# connector-32ch.net
KiCad netlist of a schematic drawn in EAGLE
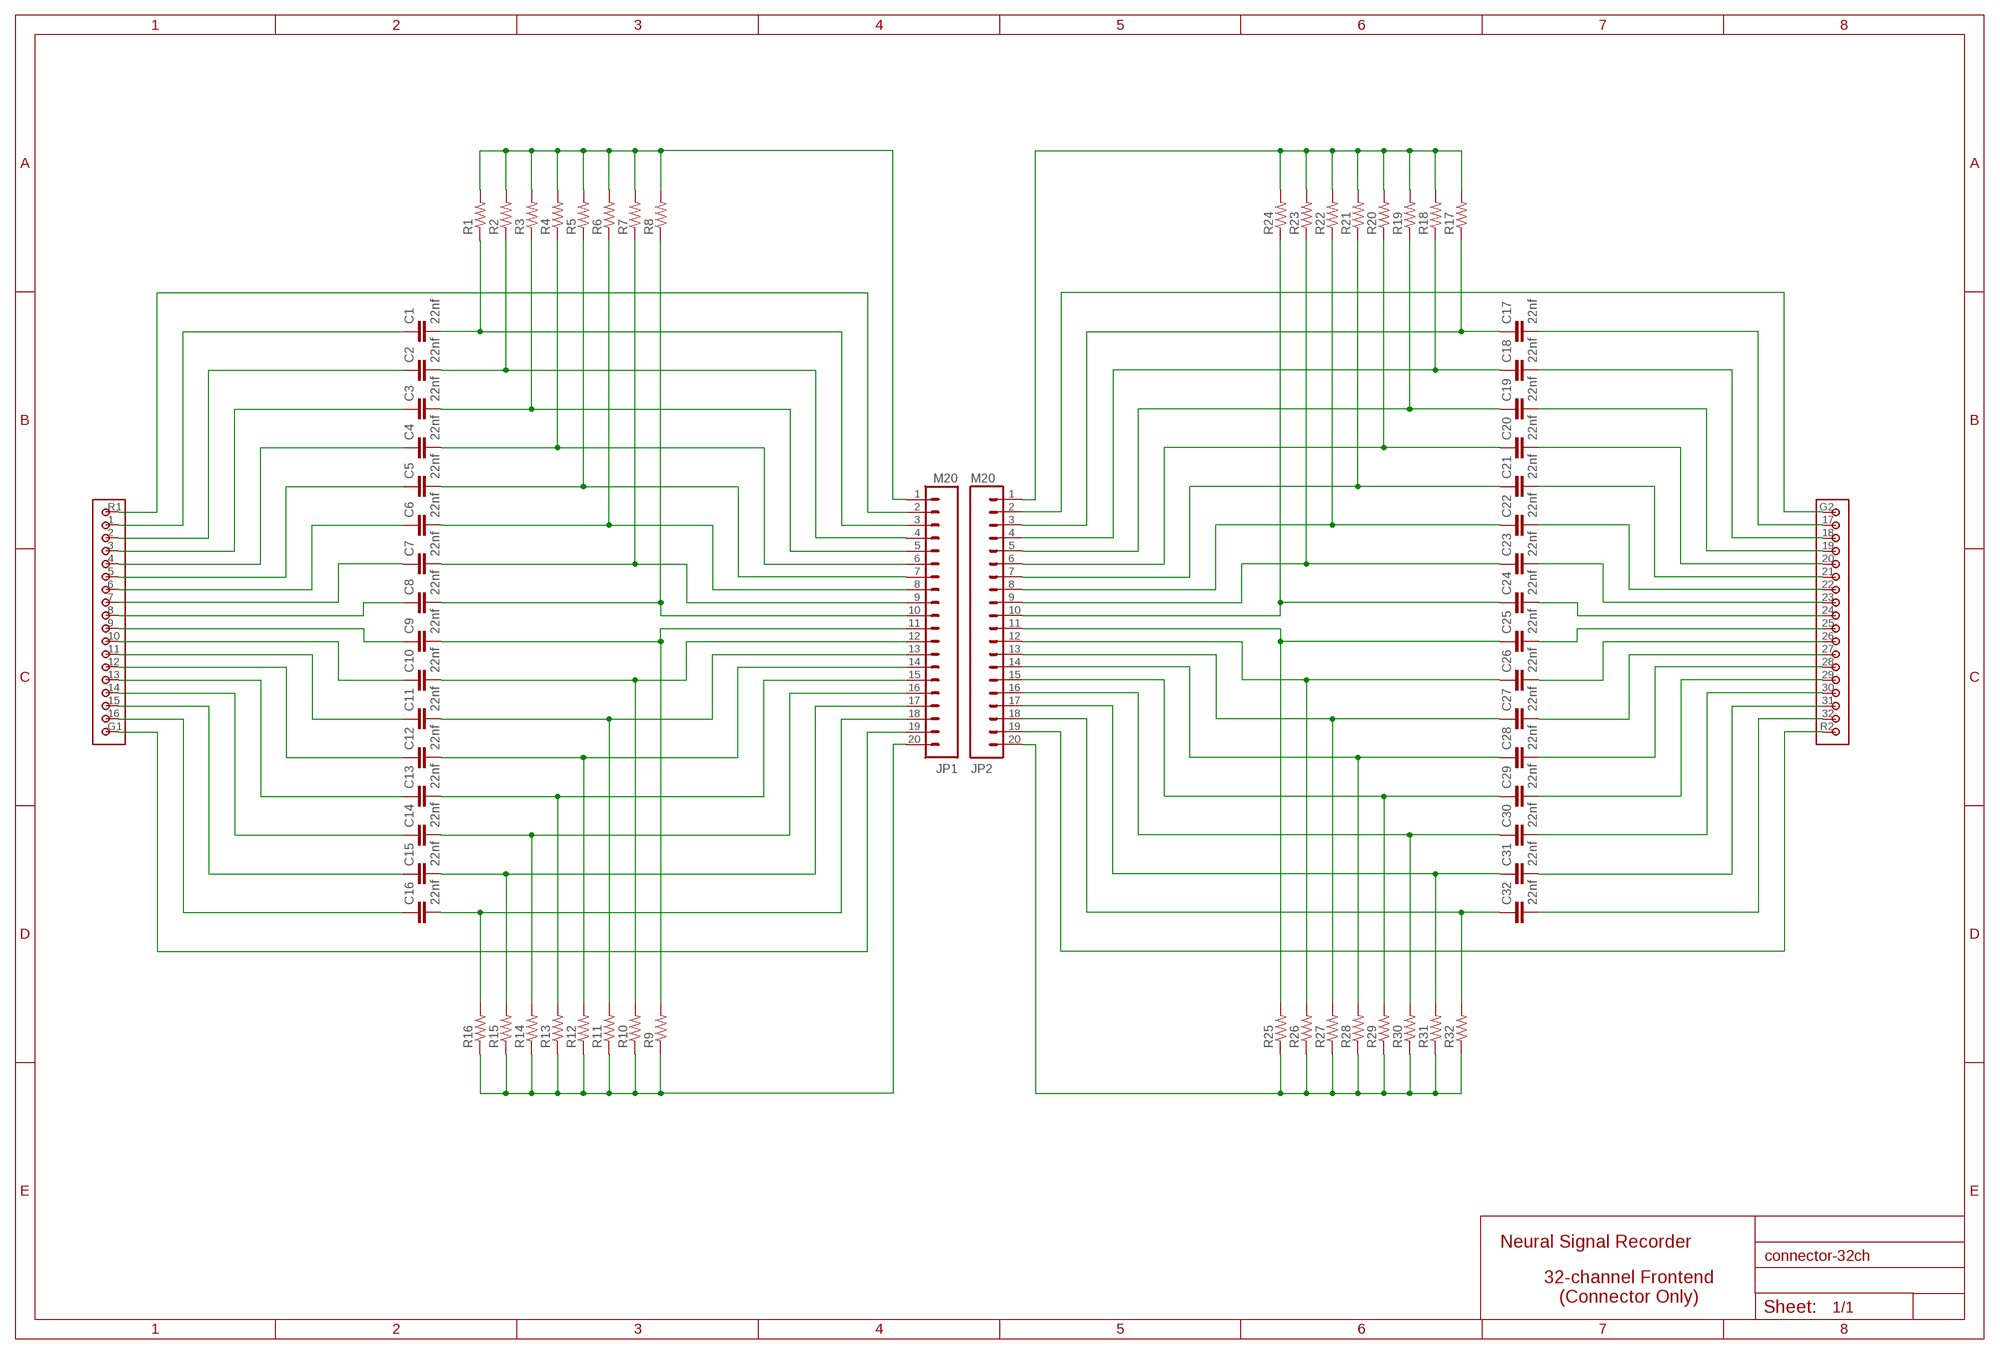
[diagram p0: schematic, sheet 1]

(export (version "E")
  (design (tool "Eeschema 10.0.6"))
  (components
    (comp (ref "C1")
      (value "22nf")
      (footprint "eagle-import:C0402")
      (libsource (lib "eagle-import") (part "C-EUC0402"))
    )
    (comp (ref "C2")
      (value "22nf")
      (footprint "eagle-import:C0402")
      (libsource (lib "eagle-import") (part "C-EUC0402"))
    )
    (comp (ref "C3")
      (value "22nf")
      (footprint "eagle-import:C0402")
      (libsource (lib "eagle-import") (part "C-EUC0402"))
    )
    (comp (ref "C4")
      (value "22nf")
      (footprint "eagle-import:C0402")
      (libsource (lib "eagle-import") (part "C-EUC0402"))
    )
    (comp (ref "C5")
      (value "22nf")
      (footprint "eagle-import:C0402")
      (libsource (lib "eagle-import") (part "C-EUC0402"))
    )
    (comp (ref "C6")
      (value "22nf")
      (footprint "eagle-import:C0402")
      (libsource (lib "eagle-import") (part "C-EUC0402"))
    )
    (comp (ref "C7")
      (value "22nf")
      (footprint "eagle-import:C0402")
      (libsource (lib "eagle-import") (part "C-EUC0402"))
    )
    (comp (ref "C8")
      (value "22nf")
      (footprint "eagle-import:C0402")
      (libsource (lib "eagle-import") (part "C-EUC0402"))
    )
    (comp (ref "C9")
      (value "22nf")
      (footprint "eagle-import:C0402")
      (libsource (lib "eagle-import") (part "C-EUC0402"))
    )
    (comp (ref "C10")
      (value "22nf")
      (footprint "eagle-import:C0402")
      (libsource (lib "eagle-import") (part "C-EUC0402"))
    )
    (comp (ref "C11")
      (value "22nf")
      (footprint "eagle-import:C0402")
      (libsource (lib "eagle-import") (part "C-EUC0402"))
    )
    (comp (ref "C12")
      (value "22nf")
      (footprint "eagle-import:C0402")
      (libsource (lib "eagle-import") (part "C-EUC0402"))
    )
    (comp (ref "C13")
      (value "22nf")
      (footprint "eagle-import:C0402")
      (libsource (lib "eagle-import") (part "C-EUC0402"))
    )
    (comp (ref "C14")
      (value "22nf")
      (footprint "eagle-import:C0402")
      (libsource (lib "eagle-import") (part "C-EUC0402"))
    )
    (comp (ref "C15")
      (value "22nf")
      (footprint "eagle-import:C0402")
      (libsource (lib "eagle-import") (part "C-EUC0402"))
    )
    (comp (ref "C16")
      (value "22nf")
      (footprint "eagle-import:C0402")
      (libsource (lib "eagle-import") (part "C-EUC0402"))
    )
    (comp (ref "C17")
      (value "22nf")
      (footprint "eagle-import:C0402")
      (libsource (lib "eagle-import") (part "C-EUC0402"))
    )
    (comp (ref "C18")
      (value "22nf")
      (footprint "eagle-import:C0402")
      (libsource (lib "eagle-import") (part "C-EUC0402"))
    )
    (comp (ref "C19")
      (value "22nf")
      (footprint "eagle-import:C0402")
      (libsource (lib "eagle-import") (part "C-EUC0402"))
    )
    (comp (ref "C20")
      (value "22nf")
      (footprint "eagle-import:C0402")
      (libsource (lib "eagle-import") (part "C-EUC0402"))
    )
    (comp (ref "C21")
      (value "22nf")
      (footprint "eagle-import:C0402")
      (libsource (lib "eagle-import") (part "C-EUC0402"))
    )
    (comp (ref "C22")
      (value "22nf")
      (footprint "eagle-import:C0402")
      (libsource (lib "eagle-import") (part "C-EUC0402"))
    )
    (comp (ref "C23")
      (value "22nf")
      (footprint "eagle-import:C0402")
      (libsource (lib "eagle-import") (part "C-EUC0402"))
    )
    (comp (ref "C24")
      (value "22nf")
      (footprint "eagle-import:C0402")
      (libsource (lib "eagle-import") (part "C-EUC0402"))
    )
    (comp (ref "C25")
      (value "22nf")
      (footprint "eagle-import:C0402")
      (libsource (lib "eagle-import") (part "C-EUC0402"))
    )
    (comp (ref "C26")
      (value "22nf")
      (footprint "eagle-import:C0402")
      (libsource (lib "eagle-import") (part "C-EUC0402"))
    )
    (comp (ref "C27")
      (value "22nf")
      (footprint "eagle-import:C0402")
      (libsource (lib "eagle-import") (part "C-EUC0402"))
    )
    (comp (ref "C28")
      (value "22nf")
      (footprint "eagle-import:C0402")
      (libsource (lib "eagle-import") (part "C-EUC0402"))
    )
    (comp (ref "C29")
      (value "22nf")
      (footprint "eagle-import:C0402")
      (libsource (lib "eagle-import") (part "C-EUC0402"))
    )
    (comp (ref "C30")
      (value "22nf")
      (footprint "eagle-import:C0402")
      (libsource (lib "eagle-import") (part "C-EUC0402"))
    )
    (comp (ref "C31")
      (value "22nf")
      (footprint "eagle-import:C0402")
      (libsource (lib "eagle-import") (part "C-EUC0402"))
    )
    (comp (ref "C32")
      (value "22nf")
      (footprint "eagle-import:C0402")
      (libsource (lib "eagle-import") (part "C-EUC0402"))
    )
    (comp (ref "JP1")
      (value "M20")
      (footprint "eagle-import:1X20")
      (libsource (lib "eagle-import") (part "M20"))
    )
    (comp (ref "JP2")
      (value "M20")
      (footprint "eagle-import:1X20")
      (libsource (lib "eagle-import") (part "M20"))
    )
    (comp (ref "R1")
      (value "R-US_R0402")
      (footprint "eagle-import:R0402")
      (libsource (lib "eagle-import") (part "R-US_R0402"))
    )
    (comp (ref "R2")
      (value "R-US_R0402")
      (footprint "eagle-import:R0402")
      (libsource (lib "eagle-import") (part "R-US_R0402"))
    )
    (comp (ref "R3")
      (value "R-US_R0402")
      (footprint "eagle-import:R0402")
      (libsource (lib "eagle-import") (part "R-US_R0402"))
    )
    (comp (ref "R4")
      (value "R-US_R0402")
      (footprint "eagle-import:R0402")
      (libsource (lib "eagle-import") (part "R-US_R0402"))
    )
    (comp (ref "R5")
      (value "R-US_R0402")
      (footprint "eagle-import:R0402")
      (libsource (lib "eagle-import") (part "R-US_R0402"))
    )
    (comp (ref "R6")
      (value "R-US_R0402")
      (footprint "eagle-import:R0402")
      (libsource (lib "eagle-import") (part "R-US_R0402"))
    )
    (comp (ref "R7")
      (value "R-US_R0402")
      (footprint "eagle-import:R0402")
      (libsource (lib "eagle-import") (part "R-US_R0402"))
    )
    (comp (ref "R8")
      (value "R-US_R0402")
      (footprint "eagle-import:R0402")
      (libsource (lib "eagle-import") (part "R-US_R0402"))
    )
    (comp (ref "R9")
      (value "R-US_R0402")
      (footprint "eagle-import:R0402")
      (libsource (lib "eagle-import") (part "R-US_R0402"))
    )
    (comp (ref "R10")
      (value "R-US_R0402")
      (footprint "eagle-import:R0402")
      (libsource (lib "eagle-import") (part "R-US_R0402"))
    )
    (comp (ref "R11")
      (value "R-US_R0402")
      (footprint "eagle-import:R0402")
      (libsource (lib "eagle-import") (part "R-US_R0402"))
    )
    (comp (ref "R12")
      (value "R-US_R0402")
      (footprint "eagle-import:R0402")
      (libsource (lib "eagle-import") (part "R-US_R0402"))
    )
    (comp (ref "R13")
      (value "R-US_R0402")
      (footprint "eagle-import:R0402")
      (libsource (lib "eagle-import") (part "R-US_R0402"))
    )
    (comp (ref "R14")
      (value "R-US_R0402")
      (footprint "eagle-import:R0402")
      (libsource (lib "eagle-import") (part "R-US_R0402"))
    )
    (comp (ref "R15")
      (value "R-US_R0402")
      (footprint "eagle-import:R0402")
      (libsource (lib "eagle-import") (part "R-US_R0402"))
    )
    (comp (ref "R16")
      (value "R-US_R0402")
      (footprint "eagle-import:R0402")
      (libsource (lib "eagle-import") (part "R-US_R0402"))
    )
    (comp (ref "R17")
      (value "R-US_R0402")
      (footprint "eagle-import:R0402")
      (libsource (lib "eagle-import") (part "R-US_R0402"))
    )
    (comp (ref "R18")
      (value "R-US_R0402")
      (footprint "eagle-import:R0402")
      (libsource (lib "eagle-import") (part "R-US_R0402"))
    )
    (comp (ref "R19")
      (value "R-US_R0402")
      (footprint "eagle-import:R0402")
      (libsource (lib "eagle-import") (part "R-US_R0402"))
    )
    (comp (ref "R20")
      (value "R-US_R0402")
      (footprint "eagle-import:R0402")
      (libsource (lib "eagle-import") (part "R-US_R0402"))
    )
    (comp (ref "R21")
      (value "R-US_R0402")
      (footprint "eagle-import:R0402")
      (libsource (lib "eagle-import") (part "R-US_R0402"))
    )
    (comp (ref "R22")
      (value "R-US_R0402")
      (footprint "eagle-import:R0402")
      (libsource (lib "eagle-import") (part "R-US_R0402"))
    )
    (comp (ref "R23")
      (value "R-US_R0402")
      (footprint "eagle-import:R0402")
      (libsource (lib "eagle-import") (part "R-US_R0402"))
    )
    (comp (ref "R24")
      (value "R-US_R0402")
      (footprint "eagle-import:R0402")
      (libsource (lib "eagle-import") (part "R-US_R0402"))
    )
    (comp (ref "R25")
      (value "R-US_R0402")
      (footprint "eagle-import:R0402")
      (libsource (lib "eagle-import") (part "R-US_R0402"))
    )
    (comp (ref "R26")
      (value "R-US_R0402")
      (footprint "eagle-import:R0402")
      (libsource (lib "eagle-import") (part "R-US_R0402"))
    )
    (comp (ref "R27")
      (value "R-US_R0402")
      (footprint "eagle-import:R0402")
      (libsource (lib "eagle-import") (part "R-US_R0402"))
    )
    (comp (ref "R28")
      (value "R-US_R0402")
      (footprint "eagle-import:R0402")
      (libsource (lib "eagle-import") (part "R-US_R0402"))
    )
    (comp (ref "R29")
      (value "R-US_R0402")
      (footprint "eagle-import:R0402")
      (libsource (lib "eagle-import") (part "R-US_R0402"))
    )
    (comp (ref "R30")
      (value "R-US_R0402")
      (footprint "eagle-import:R0402")
      (libsource (lib "eagle-import") (part "R-US_R0402"))
    )
    (comp (ref "R31")
      (value "R-US_R0402")
      (footprint "eagle-import:R0402")
      (libsource (lib "eagle-import") (part "R-US_R0402"))
    )
    (comp (ref "R32")
      (value "R-US_R0402")
      (footprint "eagle-import:R0402")
      (libsource (lib "eagle-import") (part "R-US_R0402"))
    )
    (comp (ref "X1")
      (value "OMNETICS_36PAD")
      (footprint "eagle-import:OMNETICS36PADSMT")
      (libsource (lib "eagle-import") (part "OMNETICS_36PAD"))
    )
  )
  (nets
    (net (code "1") (name "/G") (class "Default")
      (node (ref "JP1") (pin "2") (pinfunction "2_2") (pintype "passive"))
      (node (ref "JP2") (pin "19") (pinfunction "19_19") (pintype "passive"))
      (node (ref "X1") (pin "R1") (pinfunction "P$1_R1") (pintype "passive"))
      (node (ref "X1") (pin "R2") (pinfunction "P$18_R2") (pintype "passive"))
    )
    (net (code "2") (name "/R") (class "Default")
      (node (ref "JP1") (pin "19") (pinfunction "19_19") (pintype "passive"))
      (node (ref "JP2") (pin "2") (pinfunction "2_2") (pintype "passive"))
      (node (ref "X1") (pin "G1") (pinfunction "P$18_G1") (pintype "passive"))
      (node (ref "X1") (pin "G2") (pinfunction "P$1_G2") (pintype "passive"))
    )
    (net (code "3") (name "/VCM") (class "Default")
      (node (ref "JP1") (pin "1") (pinfunction "1_1") (pintype "passive"))
      (node (ref "JP1") (pin "20") (pinfunction "20_20") (pintype "passive"))
      (node (ref "JP2") (pin "1") (pinfunction "1_1") (pintype "passive"))
      (node (ref "JP2") (pin "20") (pinfunction "20_20") (pintype "passive"))
      (node (ref "R1") (pin "2") (pinfunction "2_2") (pintype "passive"))
      (node (ref "R10") (pin "1") (pinfunction "1_1") (pintype "passive"))
      (node (ref "R11") (pin "1") (pinfunction "1_1") (pintype "passive"))
      (node (ref "R12") (pin "1") (pinfunction "1_1") (pintype "passive"))
      (node (ref "R13") (pin "1") (pinfunction "1_1") (pintype "passive"))
      (node (ref "R14") (pin "1") (pinfunction "1_1") (pintype "passive"))
      (node (ref "R15") (pin "1") (pinfunction "1_1") (pintype "passive"))
      (node (ref "R16") (pin "1") (pinfunction "1_1") (pintype "passive"))
      (node (ref "R17") (pin "2") (pinfunction "2_2") (pintype "passive"))
      (node (ref "R18") (pin "2") (pinfunction "2_2") (pintype "passive"))
      (node (ref "R19") (pin "2") (pinfunction "2_2") (pintype "passive"))
      (node (ref "R2") (pin "2") (pinfunction "2_2") (pintype "passive"))
      (node (ref "R20") (pin "2") (pinfunction "2_2") (pintype "passive"))
      (node (ref "R21") (pin "2") (pinfunction "2_2") (pintype "passive"))
      (node (ref "R22") (pin "2") (pinfunction "2_2") (pintype "passive"))
      (node (ref "R23") (pin "2") (pinfunction "2_2") (pintype "passive"))
      (node (ref "R24") (pin "2") (pinfunction "2_2") (pintype "passive"))
      (node (ref "R25") (pin "1") (pinfunction "1_1") (pintype "passive"))
      (node (ref "R26") (pin "1") (pinfunction "1_1") (pintype "passive"))
      (node (ref "R27") (pin "1") (pinfunction "1_1") (pintype "passive"))
      (node (ref "R28") (pin "1") (pinfunction "1_1") (pintype "passive"))
      (node (ref "R29") (pin "1") (pinfunction "1_1") (pintype "passive"))
      (node (ref "R3") (pin "2") (pinfunction "2_2") (pintype "passive"))
      (node (ref "R30") (pin "1") (pinfunction "1_1") (pintype "passive"))
      (node (ref "R31") (pin "1") (pinfunction "1_1") (pintype "passive"))
      (node (ref "R32") (pin "1") (pinfunction "1_1") (pintype "passive"))
      (node (ref "R4") (pin "2") (pinfunction "2_2") (pintype "passive"))
      (node (ref "R5") (pin "2") (pinfunction "2_2") (pintype "passive"))
      (node (ref "R6") (pin "2") (pinfunction "2_2") (pintype "passive"))
      (node (ref "R7") (pin "2") (pinfunction "2_2") (pintype "passive"))
      (node (ref "R8") (pin "2") (pinfunction "2_2") (pintype "passive"))
      (node (ref "R9") (pin "1") (pinfunction "1_1") (pintype "passive"))
    )
    (net (code "4") (name "Net-(C1-Pad2)") (class "Default")
      (node (ref "C1") (pin "2") (pinfunction "2_2") (pintype "passive"))
      (node (ref "JP1") (pin "3") (pinfunction "3_3") (pintype "passive"))
      (node (ref "R1") (pin "1") (pinfunction "1_1") (pintype "passive"))
    )
    (net (code "5") (name "Net-(C2-Pad2)") (class "Default")
      (node (ref "C2") (pin "2") (pinfunction "2_2") (pintype "passive"))
      (node (ref "JP1") (pin "4") (pinfunction "4_4") (pintype "passive"))
      (node (ref "R2") (pin "1") (pinfunction "1_1") (pintype "passive"))
    )
    (net (code "6") (name "Net-(C3-Pad2)") (class "Default")
      (node (ref "C3") (pin "2") (pinfunction "2_2") (pintype "passive"))
      (node (ref "JP1") (pin "5") (pinfunction "5_5") (pintype "passive"))
      (node (ref "R3") (pin "1") (pinfunction "1_1") (pintype "passive"))
    )
    (net (code "7") (name "Net-(C4-Pad2)") (class "Default")
      (node (ref "C4") (pin "2") (pinfunction "2_2") (pintype "passive"))
      (node (ref "JP1") (pin "6") (pinfunction "6_6") (pintype "passive"))
      (node (ref "R4") (pin "1") (pinfunction "1_1") (pintype "passive"))
    )
    (net (code "8") (name "Net-(C5-Pad2)") (class "Default")
      (node (ref "C5") (pin "2") (pinfunction "2_2") (pintype "passive"))
      (node (ref "JP1") (pin "7") (pinfunction "7_7") (pintype "passive"))
      (node (ref "R5") (pin "1") (pinfunction "1_1") (pintype "passive"))
    )
    (net (code "9") (name "Net-(C6-Pad2)") (class "Default")
      (node (ref "C6") (pin "2") (pinfunction "2_2") (pintype "passive"))
      (node (ref "JP1") (pin "8") (pinfunction "8_8") (pintype "passive"))
      (node (ref "R6") (pin "1") (pinfunction "1_1") (pintype "passive"))
    )
    (net (code "10") (name "Net-(C7-Pad2)") (class "Default")
      (node (ref "C7") (pin "2") (pinfunction "2_2") (pintype "passive"))
      (node (ref "JP1") (pin "9") (pinfunction "9_9") (pintype "passive"))
      (node (ref "R7") (pin "1") (pinfunction "1_1") (pintype "passive"))
    )
    (net (code "11") (name "Net-(C8-Pad2)") (class "Default")
      (node (ref "C8") (pin "2") (pinfunction "2_2") (pintype "passive"))
      (node (ref "JP1") (pin "10") (pinfunction "10_10") (pintype "passive"))
      (node (ref "R8") (pin "1") (pinfunction "1_1") (pintype "passive"))
    )
    (net (code "12") (name "Net-(C9-Pad2)") (class "Default")
      (node (ref "C9") (pin "2") (pinfunction "2_2") (pintype "passive"))
      (node (ref "JP1") (pin "11") (pinfunction "11_11") (pintype "passive"))
      (node (ref "R9") (pin "2") (pinfunction "2_2") (pintype "passive"))
    )
    (net (code "13") (name "Net-(C10-Pad2)") (class "Default")
      (node (ref "C10") (pin "2") (pinfunction "2_2") (pintype "passive"))
      (node (ref "JP1") (pin "12") (pinfunction "12_12") (pintype "passive"))
      (node (ref "R10") (pin "2") (pinfunction "2_2") (pintype "passive"))
    )
    (net (code "14") (name "Net-(C11-Pad2)") (class "Default")
      (node (ref "C11") (pin "2") (pinfunction "2_2") (pintype "passive"))
      (node (ref "JP1") (pin "13") (pinfunction "13_13") (pintype "passive"))
      (node (ref "R11") (pin "2") (pinfunction "2_2") (pintype "passive"))
    )
    (net (code "15") (name "Net-(C12-Pad2)") (class "Default")
      (node (ref "C12") (pin "2") (pinfunction "2_2") (pintype "passive"))
      (node (ref "JP1") (pin "14") (pinfunction "14_14") (pintype "passive"))
      (node (ref "R12") (pin "2") (pinfunction "2_2") (pintype "passive"))
    )
    (net (code "16") (name "Net-(C13-Pad2)") (class "Default")
      (node (ref "C13") (pin "2") (pinfunction "2_2") (pintype "passive"))
      (node (ref "JP1") (pin "15") (pinfunction "15_15") (pintype "passive"))
      (node (ref "R13") (pin "2") (pinfunction "2_2") (pintype "passive"))
    )
    (net (code "17") (name "Net-(C14-Pad2)") (class "Default")
      (node (ref "C14") (pin "2") (pinfunction "2_2") (pintype "passive"))
      (node (ref "JP1") (pin "16") (pinfunction "16_16") (pintype "passive"))
      (node (ref "R14") (pin "2") (pinfunction "2_2") (pintype "passive"))
    )
    (net (code "18") (name "Net-(C15-Pad2)") (class "Default")
      (node (ref "C15") (pin "2") (pinfunction "2_2") (pintype "passive"))
      (node (ref "JP1") (pin "17") (pinfunction "17_17") (pintype "passive"))
      (node (ref "R15") (pin "2") (pinfunction "2_2") (pintype "passive"))
    )
    (net (code "19") (name "Net-(C16-Pad2)") (class "Default")
      (node (ref "C16") (pin "2") (pinfunction "2_2") (pintype "passive"))
      (node (ref "JP1") (pin "18") (pinfunction "18_18") (pintype "passive"))
      (node (ref "R16") (pin "2") (pinfunction "2_2") (pintype "passive"))
    )
    (net (code "20") (name "Net-(C17-Pad1)") (class "Default")
      (node (ref "C17") (pin "1") (pinfunction "1_1") (pintype "passive"))
      (node (ref "JP2") (pin "3") (pinfunction "3_3") (pintype "passive"))
      (node (ref "R17") (pin "1") (pinfunction "1_1") (pintype "passive"))
    )
    (net (code "21") (name "Net-(C18-Pad1)") (class "Default")
      (node (ref "C18") (pin "1") (pinfunction "1_1") (pintype "passive"))
      (node (ref "JP2") (pin "4") (pinfunction "4_4") (pintype "passive"))
      (node (ref "R18") (pin "1") (pinfunction "1_1") (pintype "passive"))
    )
    (net (code "22") (name "Net-(C19-Pad1)") (class "Default")
      (node (ref "C19") (pin "1") (pinfunction "1_1") (pintype "passive"))
      (node (ref "JP2") (pin "5") (pinfunction "5_5") (pintype "passive"))
      (node (ref "R19") (pin "1") (pinfunction "1_1") (pintype "passive"))
    )
    (net (code "23") (name "Net-(C20-Pad1)") (class "Default")
      (node (ref "C20") (pin "1") (pinfunction "1_1") (pintype "passive"))
      (node (ref "JP2") (pin "6") (pinfunction "6_6") (pintype "passive"))
      (node (ref "R20") (pin "1") (pinfunction "1_1") (pintype "passive"))
    )
    (net (code "24") (name "Net-(C21-Pad1)") (class "Default")
      (node (ref "C21") (pin "1") (pinfunction "1_1") (pintype "passive"))
      (node (ref "JP2") (pin "7") (pinfunction "7_7") (pintype "passive"))
      (node (ref "R21") (pin "1") (pinfunction "1_1") (pintype "passive"))
    )
    (net (code "25") (name "Net-(C22-Pad1)") (class "Default")
      (node (ref "C22") (pin "1") (pinfunction "1_1") (pintype "passive"))
      (node (ref "JP2") (pin "8") (pinfunction "8_8") (pintype "passive"))
      (node (ref "R22") (pin "1") (pinfunction "1_1") (pintype "passive"))
    )
    (net (code "26") (name "Net-(C23-Pad1)") (class "Default")
      (node (ref "C23") (pin "1") (pinfunction "1_1") (pintype "passive"))
      (node (ref "JP2") (pin "9") (pinfunction "9_9") (pintype "passive"))
      (node (ref "R23") (pin "1") (pinfunction "1_1") (pintype "passive"))
    )
    (net (code "27") (name "Net-(C24-Pad1)") (class "Default")
      (node (ref "C24") (pin "1") (pinfunction "1_1") (pintype "passive"))
      (node (ref "JP2") (pin "10") (pinfunction "10_10") (pintype "passive"))
      (node (ref "R24") (pin "1") (pinfunction "1_1") (pintype "passive"))
    )
    (net (code "28") (name "Net-(C25-Pad1)") (class "Default")
      (node (ref "C25") (pin "1") (pinfunction "1_1") (pintype "passive"))
      (node (ref "JP2") (pin "11") (pinfunction "11_11") (pintype "passive"))
      (node (ref "R25") (pin "2") (pinfunction "2_2") (pintype "passive"))
    )
    (net (code "29") (name "Net-(C26-Pad1)") (class "Default")
      (node (ref "C26") (pin "1") (pinfunction "1_1") (pintype "passive"))
      (node (ref "JP2") (pin "12") (pinfunction "12_12") (pintype "passive"))
      (node (ref "R26") (pin "2") (pinfunction "2_2") (pintype "passive"))
    )
    (net (code "30") (name "Net-(C27-Pad1)") (class "Default")
      (node (ref "C27") (pin "1") (pinfunction "1_1") (pintype "passive"))
      (node (ref "JP2") (pin "13") (pinfunction "13_13") (pintype "passive"))
      (node (ref "R27") (pin "2") (pinfunction "2_2") (pintype "passive"))
    )
    (net (code "31") (name "Net-(C28-Pad1)") (class "Default")
      (node (ref "C28") (pin "1") (pinfunction "1_1") (pintype "passive"))
      (node (ref "JP2") (pin "14") (pinfunction "14_14") (pintype "passive"))
      (node (ref "R28") (pin "2") (pinfunction "2_2") (pintype "passive"))
    )
    (net (code "32") (name "Net-(C29-Pad1)") (class "Default")
      (node (ref "C29") (pin "1") (pinfunction "1_1") (pintype "passive"))
      (node (ref "JP2") (pin "15") (pinfunction "15_15") (pintype "passive"))
      (node (ref "R29") (pin "2") (pinfunction "2_2") (pintype "passive"))
    )
    (net (code "33") (name "Net-(C30-Pad1)") (class "Default")
      (node (ref "C30") (pin "1") (pinfunction "1_1") (pintype "passive"))
      (node (ref "JP2") (pin "16") (pinfunction "16_16") (pintype "passive"))
      (node (ref "R30") (pin "2") (pinfunction "2_2") (pintype "passive"))
    )
    (net (code "34") (name "Net-(C31-Pad1)") (class "Default")
      (node (ref "C31") (pin "1") (pinfunction "1_1") (pintype "passive"))
      (node (ref "JP2") (pin "17") (pinfunction "17_17") (pintype "passive"))
      (node (ref "R31") (pin "2") (pinfunction "2_2") (pintype "passive"))
    )
    (net (code "35") (name "Net-(C32-Pad1)") (class "Default")
      (node (ref "C32") (pin "1") (pinfunction "1_1") (pintype "passive"))
      (node (ref "JP2") (pin "18") (pinfunction "18_18") (pintype "passive"))
      (node (ref "R32") (pin "2") (pinfunction "2_2") (pintype "passive"))
    )
    (net (code "36") (name "Net-(X1A-P$2)") (class "Default")
      (node (ref "C1") (pin "1") (pinfunction "1_1") (pintype "passive"))
      (node (ref "X1") (pin "1") (pinfunction "P$2_1") (pintype "passive"))
    )
    (net (code "37") (name "Net-(X1A-P$3)") (class "Default")
      (node (ref "C2") (pin "1") (pinfunction "1_1") (pintype "passive"))
      (node (ref "X1") (pin "2") (pinfunction "P$3_2") (pintype "passive"))
    )
    (net (code "38") (name "Net-(X1A-P$4)") (class "Default")
      (node (ref "C3") (pin "1") (pinfunction "1_1") (pintype "passive"))
      (node (ref "X1") (pin "3") (pinfunction "P$4_3") (pintype "passive"))
    )
    (net (code "39") (name "Net-(X1A-P$5)") (class "Default")
      (node (ref "C4") (pin "1") (pinfunction "1_1") (pintype "passive"))
      (node (ref "X1") (pin "4") (pinfunction "P$5_4") (pintype "passive"))
    )
    (net (code "40") (name "Net-(X1A-P$6)") (class "Default")
      (node (ref "C5") (pin "1") (pinfunction "1_1") (pintype "passive"))
      (node (ref "X1") (pin "5") (pinfunction "P$6_5") (pintype "passive"))
    )
    (net (code "41") (name "Net-(X1A-P$7)") (class "Default")
      (node (ref "C6") (pin "1") (pinfunction "1_1") (pintype "passive"))
      (node (ref "X1") (pin "6") (pinfunction "P$7_6") (pintype "passive"))
    )
    (net (code "42") (name "Net-(X1A-P$8)") (class "Default")
      (node (ref "C7") (pin "1") (pinfunction "1_1") (pintype "passive"))
      (node (ref "X1") (pin "7") (pinfunction "P$8_7") (pintype "passive"))
    )
    (net (code "43") (name "Net-(X1A-P$9)") (class "Default")
      (node (ref "C8") (pin "1") (pinfunction "1_1") (pintype "passive"))
      (node (ref "X1") (pin "8") (pinfunction "P$9_8") (pintype "passive"))
    )
    (net (code "44") (name "Net-(X1A-P$10)") (class "Default")
      (node (ref "C9") (pin "1") (pinfunction "1_1") (pintype "passive"))
      (node (ref "X1") (pin "9") (pinfunction "P$10_9") (pintype "passive"))
    )
    (net (code "45") (name "Net-(X1A-P$11)") (class "Default")
      (node (ref "C10") (pin "1") (pinfunction "1_1") (pintype "passive"))
      (node (ref "X1") (pin "10") (pinfunction "P$11_10") (pintype "passive"))
    )
    (net (code "46") (name "Net-(X1A-P$12)") (class "Default")
      (node (ref "C11") (pin "1") (pinfunction "1_1") (pintype "passive"))
      (node (ref "X1") (pin "11") (pinfunction "P$12_11") (pintype "passive"))
    )
    (net (code "47") (name "Net-(X1A-P$13)") (class "Default")
      (node (ref "C12") (pin "1") (pinfunction "1_1") (pintype "passive"))
      (node (ref "X1") (pin "12") (pinfunction "P$13_12") (pintype "passive"))
    )
    (net (code "48") (name "Net-(X1A-P$14)") (class "Default")
      (node (ref "C13") (pin "1") (pinfunction "1_1") (pintype "passive"))
      (node (ref "X1") (pin "13") (pinfunction "P$14_13") (pintype "passive"))
    )
    (net (code "49") (name "Net-(X1A-P$15)") (class "Default")
      (node (ref "C14") (pin "1") (pinfunction "1_1") (pintype "passive"))
      (node (ref "X1") (pin "14") (pinfunction "P$15_14") (pintype "passive"))
    )
    (net (code "50") (name "Net-(X1A-P$16)") (class "Default")
      (node (ref "C15") (pin "1") (pinfunction "1_1") (pintype "passive"))
      (node (ref "X1") (pin "15") (pinfunction "P$16_15") (pintype "passive"))
    )
    (net (code "51") (name "Net-(X1A-P$17)") (class "Default")
      (node (ref "C16") (pin "1") (pinfunction "1_1") (pintype "passive"))
      (node (ref "X1") (pin "16") (pinfunction "P$17_16") (pintype "passive"))
    )
    (net (code "52") (name "Net-(X1B-P$2)") (class "Default")
      (node (ref "C17") (pin "2") (pinfunction "2_2") (pintype "passive"))
      (node (ref "X1") (pin "17") (pinfunction "P$2_17") (pintype "passive"))
    )
    (net (code "53") (name "Net-(X1B-P$3)") (class "Default")
      (node (ref "C18") (pin "2") (pinfunction "2_2") (pintype "passive"))
      (node (ref "X1") (pin "18") (pinfunction "P$3_18") (pintype "passive"))
    )
    (net (code "54") (name "Net-(X1B-P$4)") (class "Default")
      (node (ref "C19") (pin "2") (pinfunction "2_2") (pintype "passive"))
      (node (ref "X1") (pin "19") (pinfunction "P$4_19") (pintype "passive"))
    )
    (net (code "55") (name "Net-(X1B-P$5)") (class "Default")
      (node (ref "C20") (pin "2") (pinfunction "2_2") (pintype "passive"))
      (node (ref "X1") (pin "20") (pinfunction "P$5_20") (pintype "passive"))
    )
    (net (code "56") (name "Net-(X1B-P$6)") (class "Default")
      (node (ref "C21") (pin "2") (pinfunction "2_2") (pintype "passive"))
      (node (ref "X1") (pin "21") (pinfunction "P$6_21") (pintype "passive"))
    )
    (net (code "57") (name "Net-(X1B-P$7)") (class "Default")
      (node (ref "C22") (pin "2") (pinfunction "2_2") (pintype "passive"))
      (node (ref "X1") (pin "22") (pinfunction "P$7_22") (pintype "passive"))
    )
    (net (code "58") (name "Net-(X1B-P$8)") (class "Default")
      (node (ref "C23") (pin "2") (pinfunction "2_2") (pintype "passive"))
      (node (ref "X1") (pin "23") (pinfunction "P$8_23") (pintype "passive"))
    )
    (net (code "59") (name "Net-(X1B-P$9)") (class "Default")
      (node (ref "C24") (pin "2") (pinfunction "2_2") (pintype "passive"))
      (node (ref "X1") (pin "24") (pinfunction "P$9_24") (pintype "passive"))
    )
    (net (code "60") (name "Net-(X1B-P$10)") (class "Default")
      (node (ref "C25") (pin "2") (pinfunction "2_2") (pintype "passive"))
      (node (ref "X1") (pin "25") (pinfunction "P$10_25") (pintype "passive"))
    )
    (net (code "61") (name "Net-(X1B-P$11)") (class "Default")
      (node (ref "C26") (pin "2") (pinfunction "2_2") (pintype "passive"))
      (node (ref "X1") (pin "26") (pinfunction "P$11_26") (pintype "passive"))
    )
    (net (code "62") (name "Net-(X1B-P$12)") (class "Default")
      (node (ref "C27") (pin "2") (pinfunction "2_2") (pintype "passive"))
      (node (ref "X1") (pin "27") (pinfunction "P$12_27") (pintype "passive"))
    )
    (net (code "63") (name "Net-(X1B-P$13)") (class "Default")
      (node (ref "C28") (pin "2") (pinfunction "2_2") (pintype "passive"))
      (node (ref "X1") (pin "28") (pinfunction "P$13_28") (pintype "passive"))
    )
    (net (code "64") (name "Net-(X1B-P$14)") (class "Default")
      (node (ref "C29") (pin "2") (pinfunction "2_2") (pintype "passive"))
      (node (ref "X1") (pin "29") (pinfunction "P$14_29") (pintype "passive"))
    )
    (net (code "65") (name "Net-(X1B-P$15)") (class "Default")
      (node (ref "C30") (pin "2") (pinfunction "2_2") (pintype "passive"))
      (node (ref "X1") (pin "30") (pinfunction "P$15_30") (pintype "passive"))
    )
    (net (code "66") (name "Net-(X1B-P$16)") (class "Default")
      (node (ref "C31") (pin "2") (pinfunction "2_2") (pintype "passive"))
      (node (ref "X1") (pin "31") (pinfunction "P$16_31") (pintype "passive"))
    )
    (net (code "67") (name "Net-(X1B-P$17)") (class "Default")
      (node (ref "C32") (pin "2") (pinfunction "2_2") (pintype "passive"))
      (node (ref "X1") (pin "32") (pinfunction "P$17_32") (pintype "passive"))
    )
  )
)
